# DDMTD.net
KiCad netlist of a schematic drawn in Altium Designer
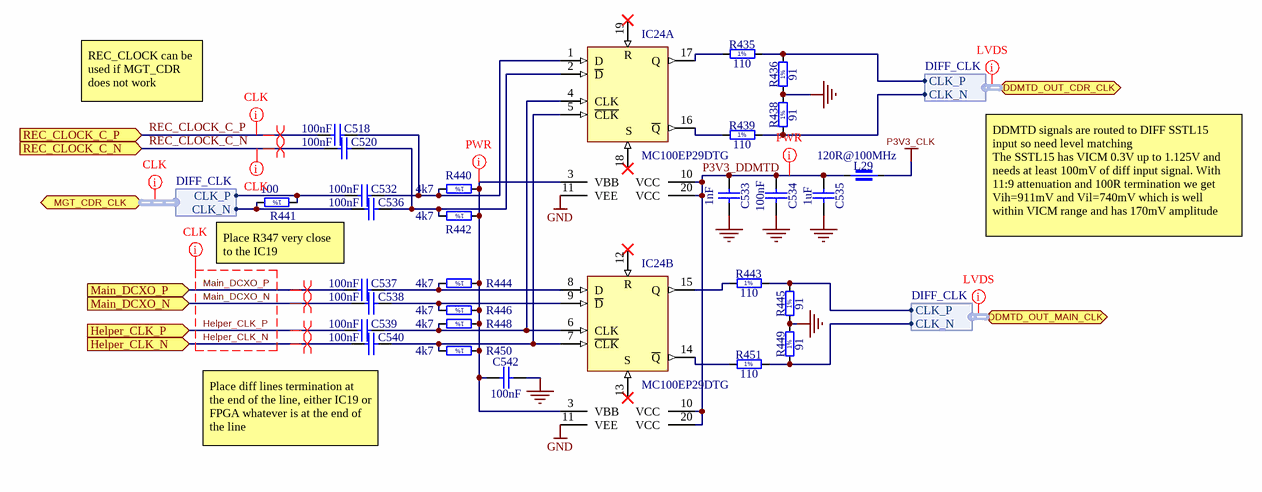
[diagram p0: DDMTD.SchDoc]

(export (version "E")
  (design (tool "Eeschema 10.0.6"))
  (components
    (comp (ref "C518")
      (value "100nF")
      (footprint "CAPC1005X55N")
      (description "Non-polarised capacitor")
      (fields
        (field (name "MANUFACTURER PART NUMBER") "CC0402_100NF_16V_10%_X5R")
        (field (name "MANUFACTURER") "GENERIC")
        (field (name "AUTHOR") "CERN DEM JLC")
      )
      (libsource (lib "Capacitors") (part "Capacitor - non polarized"))
    )
    (comp (ref "C520")
      (value "100nF")
      (footprint "CAPC1005X55N")
      (description "Non-polarised capacitor")
      (fields
        (field (name "MANUFACTURER PART NUMBER") "CC0402_100NF_16V_10%_X5R")
        (field (name "MANUFACTURER") "GENERIC")
        (field (name "AUTHOR") "CERN DEM JLC")
      )
      (libsource (lib "Capacitors") (part "Capacitor - non polarized"))
    )
    (comp (ref "C532")
      (value "100nF")
      (footprint "CAPC1005X55N")
      (description "Non-polarised capacitor")
      (fields
        (field (name "MANUFACTURER PART NUMBER") "CC0402_100NF_16V_10%_X5R")
        (field (name "MANUFACTURER") "GENERIC")
        (field (name "AUTHOR") "CERN DEM JLC")
      )
      (libsource (lib "Capacitors") (part "Capacitor - non polarized"))
    )
    (comp (ref "C533")
      (value "1nF")
      (footprint "CAPC0603X33N")
      (description "Non-polarised capacitor")
      (fields
        (field (name "MANUFACTURER PART NUMBER") "CC0201_1NF_16V_10%_X5R")
        (field (name "MANUFACTURER") "GENERIC")
        (field (name "AUTHOR") "CERN DEM JLC")
      )
      (libsource (lib "Capacitors") (part "Capacitor - non polarized"))
    )
    (comp (ref "C534")
      (value "100nF")
      (footprint "CAPC0603X33N")
      (description "Non-polarised capacitor")
      (fields
        (field (name "MANUFACTURER PART NUMBER") "CC0201_100NF_6.3V_10%_X5R")
        (field (name "MANUFACTURER") "GENERIC")
        (field (name "AUTHOR") "CERN DEM JLC")
      )
      (libsource (lib "Capacitors") (part "Capacitor - non polarized"))
    )
    (comp (ref "C535")
      (value "1uF")
      (footprint "CAPC1005X55N")
      (description "Non-polarised capacitor")
      (fields
        (field (name "MANUFACTURER PART NUMBER") "CC0402_1UF_16V_10%_X5R")
        (field (name "MANUFACTURER") "GENERIC")
        (field (name "AUTHOR") "CERN DEM JLC")
      )
      (libsource (lib "Capacitors") (part "Capacitor - non polarized"))
    )
    (comp (ref "C536")
      (value "100nF")
      (footprint "CAPC1005X55N")
      (description "Non-polarised capacitor")
      (fields
        (field (name "MANUFACTURER PART NUMBER") "CC0402_100NF_16V_10%_X5R")
        (field (name "MANUFACTURER") "GENERIC")
        (field (name "AUTHOR") "CERN DEM JLC")
      )
      (libsource (lib "Capacitors") (part "Capacitor - non polarized"))
    )
    (comp (ref "C537")
      (value "100nF")
      (footprint "CAPC1005X55N")
      (description "Non-polarised capacitor")
      (fields
        (field (name "MANUFACTURER PART NUMBER") "CC0402_100NF_16V_10%_X5R")
        (field (name "MANUFACTURER") "GENERIC")
        (field (name "AUTHOR") "CERN DEM JLC")
      )
      (libsource (lib "Capacitors") (part "Capacitor - non polarized"))
    )
    (comp (ref "C538")
      (value "100nF")
      (footprint "CAPC1005X55N")
      (description "Non-polarised capacitor")
      (fields
        (field (name "MANUFACTURER PART NUMBER") "CC0402_100NF_16V_10%_X5R")
        (field (name "MANUFACTURER") "GENERIC")
        (field (name "AUTHOR") "CERN DEM JLC")
      )
      (libsource (lib "Capacitors") (part "Capacitor - non polarized"))
    )
    (comp (ref "C539")
      (value "100nF")
      (footprint "CAPC1005X55N")
      (description "Non-polarised capacitor")
      (fields
        (field (name "MANUFACTURER PART NUMBER") "CC0402_100NF_16V_10%_X5R")
        (field (name "MANUFACTURER") "GENERIC")
        (field (name "AUTHOR") "CERN DEM JLC")
      )
      (libsource (lib "Capacitors") (part "Capacitor - non polarized"))
    )
    (comp (ref "C540")
      (value "100nF")
      (footprint "CAPC1005X55N")
      (description "Non-polarised capacitor")
      (fields
        (field (name "MANUFACTURER PART NUMBER") "CC0402_100NF_16V_10%_X5R")
        (field (name "MANUFACTURER") "GENERIC")
        (field (name "AUTHOR") "CERN DEM JLC")
      )
      (libsource (lib "Capacitors") (part "Capacitor - non polarized"))
    )
    (comp (ref "C542")
      (value "100nF")
      (footprint "CAPC0603X33N")
      (description "Non-polarised capacitor")
      (fields
        (field (name "MANUFACTURER PART NUMBER") "CC0201_100NF_6.3V_10%_X5R")
        (field (name "MANUFACTURER") "GENERIC")
        (field (name "AUTHOR") "CERN DEM JLC")
      )
      (libsource (lib "Capacitors") (part "Capacitor - non polarized"))
    )
    (comp (ref "IC24")
      (value "MC100EP29DTG")
      (footprint "SOP65P640X120-20N")
      (description "3.3V/5V ECL Dual Differential Data and Clock D Flip-Flop With Set and Reset")
      (fields (field (name "MANUFACTURER") "ON SEMICONDUCTOR") (field (name "AUTHOR") "CERN DEM JLC"))
      (libsource (lib "ICs And Semiconductors") (part "100EP29D"))
    )
    (comp (ref "L29")
      (value "120R@100MHz")
      (footprint "INDC1608X95N")
      (fields
        (field (name "MANUFACTURER PART NUMBER") "BLM18PG121SN1D")
        (field (name "MANUFACTURER") "MURATA")
        (field (name "PART NUMBER") "IND0603_MURATA_BLM18PG121SN1D")
        (field (name "AUTHOR") "CERN DEM BC")
      )
      (libsource (lib "Inductors & Transformers") (part "Ferrite Bead"))
    )
    (comp (ref "R435")
      (value "110")
      (footprint "RESC1005X40N")
      (description "Resistor - 1%")
      (fields
        (field (name "MANUFACTURER PART NUMBER") "R0402_110R_1%_0.0625W_100PPM")
        (field (name "MANUFACTURER") "GENERIC")
        (field (name "AUTHOR") "CERN DEM JLC")
      )
      (libsource (lib "Resistors") (part "Resistor - 1%"))
    )
    (comp (ref "R436")
      (value "91")
      (footprint "RESC1005X40N")
      (description "Resistor - 1%")
      (fields
        (field (name "MANUFACTURER PART NUMBER") "R0402_91R_1%_0.0625W_100PPM")
        (field (name "MANUFACTURER") "GENERIC")
        (field (name "AUTHOR") "CERN DEM JLC")
      )
      (libsource (lib "Resistors") (part "Resistor - 1%"))
    )
    (comp (ref "R438")
      (value "91")
      (footprint "RESC1005X40N")
      (description "Resistor - 1%")
      (fields
        (field (name "MANUFACTURER PART NUMBER") "R0402_91R_1%_0.0625W_100PPM")
        (field (name "MANUFACTURER") "GENERIC")
        (field (name "AUTHOR") "CERN DEM JLC")
      )
      (libsource (lib "Resistors") (part "Resistor - 1%"))
    )
    (comp (ref "R439")
      (value "110")
      (footprint "RESC1005X40N")
      (description "Resistor - 1%")
      (fields
        (field (name "MANUFACTURER PART NUMBER") "R0402_110R_1%_0.0625W_100PPM")
        (field (name "MANUFACTURER") "GENERIC")
        (field (name "AUTHOR") "CERN DEM JLC")
      )
      (libsource (lib "Resistors") (part "Resistor - 1%"))
    )
    (comp (ref "R440")
      (value "4k7")
      (footprint "RESC1005X40N")
      (description "Resistor - 1%")
      (fields
        (field (name "MANUFACTURER PART NUMBER") "R0402_4K7_1%_0.0625W_100PPM")
        (field (name "MANUFACTURER") "GENERIC")
        (field (name "AUTHOR") "CERN DEM JLC")
      )
      (libsource (lib "Resistors") (part "Resistor - 1%"))
    )
    (comp (ref "R441")
      (value "100")
      (footprint "RESC1005X40N")
      (description "Resistor - 1%")
      (fields
        (field (name "MANUFACTURER PART NUMBER") "R0402_100R_1%_0.0625W_100PPM")
        (field (name "MANUFACTURER") "GENERIC")
        (field (name "AUTHOR") "CERN DEM JLC")
      )
      (libsource (lib "Resistors") (part "Resistor - 1%"))
    )
    (comp (ref "R442")
      (value "4k7")
      (footprint "RESC1005X40N")
      (description "Resistor - 1%")
      (fields
        (field (name "MANUFACTURER PART NUMBER") "R0402_4K7_1%_0.0625W_100PPM")
        (field (name "MANUFACTURER") "GENERIC")
        (field (name "AUTHOR") "CERN DEM JLC")
      )
      (libsource (lib "Resistors") (part "Resistor - 1%"))
    )
    (comp (ref "R443")
      (value "110")
      (footprint "RESC1005X40N")
      (description "Resistor - 1%")
      (fields
        (field (name "MANUFACTURER PART NUMBER") "R0402_110R_1%_0.0625W_100PPM")
        (field (name "MANUFACTURER") "GENERIC")
        (field (name "AUTHOR") "CERN DEM JLC")
      )
      (libsource (lib "Resistors") (part "Resistor - 1%"))
    )
    (comp (ref "R444")
      (value "4k7")
      (footprint "RESC1005X40N")
      (description "Resistor - 1%")
      (fields
        (field (name "MANUFACTURER PART NUMBER") "R0402_4K7_1%_0.0625W_100PPM")
        (field (name "MANUFACTURER") "GENERIC")
        (field (name "AUTHOR") "CERN DEM JLC")
      )
      (libsource (lib "Resistors") (part "Resistor - 1%"))
    )
    (comp (ref "R445")
      (value "91")
      (footprint "RESC1005X40N")
      (description "Resistor - 1%")
      (fields
        (field (name "MANUFACTURER PART NUMBER") "R0402_91R_1%_0.0625W_100PPM")
        (field (name "MANUFACTURER") "GENERIC")
        (field (name "AUTHOR") "CERN DEM JLC")
      )
      (libsource (lib "Resistors") (part "Resistor - 1%"))
    )
    (comp (ref "R446")
      (value "4k7")
      (footprint "RESC1005X40N")
      (description "Resistor - 1%")
      (fields
        (field (name "MANUFACTURER PART NUMBER") "R0402_4K7_1%_0.0625W_100PPM")
        (field (name "MANUFACTURER") "GENERIC")
        (field (name "AUTHOR") "CERN DEM JLC")
      )
      (libsource (lib "Resistors") (part "Resistor - 1%"))
    )
    (comp (ref "R448")
      (value "4k7")
      (footprint "RESC1005X40N")
      (description "Resistor - 1%")
      (fields
        (field (name "MANUFACTURER PART NUMBER") "R0402_4K7_1%_0.0625W_100PPM")
        (field (name "MANUFACTURER") "GENERIC")
        (field (name "AUTHOR") "CERN DEM JLC")
      )
      (libsource (lib "Resistors") (part "Resistor - 1%"))
    )
    (comp (ref "R449")
      (value "91")
      (footprint "RESC1005X40N")
      (description "Resistor - 1%")
      (fields
        (field (name "MANUFACTURER PART NUMBER") "R0402_91R_1%_0.0625W_100PPM")
        (field (name "MANUFACTURER") "GENERIC")
        (field (name "AUTHOR") "CERN DEM JLC")
      )
      (libsource (lib "Resistors") (part "Resistor - 1%"))
    )
    (comp (ref "R450")
      (value "4k7")
      (footprint "RESC1005X40N")
      (description "Resistor - 1%")
      (fields
        (field (name "MANUFACTURER PART NUMBER") "R0402_4K7_1%_0.0625W_100PPM")
        (field (name "MANUFACTURER") "GENERIC")
        (field (name "AUTHOR") "CERN DEM JLC")
      )
      (libsource (lib "Resistors") (part "Resistor - 1%"))
    )
    (comp (ref "R451")
      (value "110")
      (footprint "RESC1005X40N")
      (description "Resistor - 1%")
      (fields
        (field (name "MANUFACTURER PART NUMBER") "R0402_110R_1%_0.0625W_100PPM")
        (field (name "MANUFACTURER") "GENERIC")
        (field (name "AUTHOR") "CERN DEM JLC")
      )
      (libsource (lib "Resistors") (part "Resistor - 1%"))
    )
  )
  (nets
    (net (code "2") (name "/Helper_CLK_N") (class "Default")
      (node (ref "C540") (pin "1") (pinfunction "1_1") (pintype "passive"))
    )
    (net (code "3") (name "/Helper_CLK_P") (class "Default")
      (node (ref "C539") (pin "1") (pinfunction "1_1") (pintype "passive"))
    )
    (net (code "4") (name "/Main_DCXO_N") (class "Default")
      (node (ref "C538") (pin "1") (pinfunction "1_1") (pintype "passive"))
    )
    (net (code "5") (name "/Main_DCXO_P") (class "Default")
      (node (ref "C537") (pin "1") (pinfunction "1_1") (pintype "passive"))
    )
    (net (code "6") (name "/P3V3_DDMTD") (class "Default")
      (node (ref "C533") (pin "2") (pinfunction "2_2") (pintype "passive"))
      (node (ref "C534") (pin "2") (pinfunction "2_2") (pintype "passive"))
      (node (ref "C535") (pin "1") (pinfunction "1_1") (pintype "passive"))
      (node (ref "IC24") (pin "10") (pinfunction "VCC_10") (pintype "power_in"))
      (node (ref "IC24") (pin "20") (pinfunction "VCC_20") (pintype "power_in"))
      (node (ref "L29") (pin "2") (pinfunction "2_2") (pintype "passive"))
    )
    (net (code "7") (name "/REC_CLOCK_C_N") (class "Default")
      (node (ref "C520") (pin "1") (pinfunction "1_1") (pintype "passive"))
    )
    (net (code "8") (name "/REC_CLOCK_C_P") (class "Default")
      (node (ref "C518") (pin "1") (pinfunction "1_1") (pintype "passive"))
    )
    (net (code "10") (name "GND") (class "Default")
      (node (ref "C533") (pin "1") (pinfunction "1_1") (pintype "passive"))
      (node (ref "C534") (pin "1") (pinfunction "1_1") (pintype "passive"))
      (node (ref "C535") (pin "2") (pinfunction "2_2") (pintype "passive"))
      (node (ref "C542") (pin "1") (pinfunction "1_1") (pintype "passive"))
      (node (ref "IC24") (pin "11") (pinfunction "VEE_11") (pintype "power_in"))
      (node (ref "R436") (pin "1") (pinfunction "1_1") (pintype "passive"))
      (node (ref "R438") (pin "2") (pinfunction "2_2") (pintype "passive"))
      (node (ref "R445") (pin "1") (pinfunction "1_1") (pintype "passive"))
      (node (ref "R449") (pin "2") (pinfunction "2_2") (pintype "passive"))
    )
    (net (code "11") (name "Net-(C532-Pad1)") (class "Default")
      (node (ref "C532") (pin "1") (pinfunction "1_1") (pintype "passive"))
      (node (ref "R441") (pin "1") (pinfunction "1_1") (pintype "passive"))
    )
    (net (code "12") (name "Net-(C536-Pad1)") (class "Default")
      (node (ref "C536") (pin "1") (pinfunction "1_1") (pintype "passive"))
      (node (ref "R441") (pin "2") (pinfunction "2_2") (pintype "passive"))
    )
    (net (code "13") (name "Net-(IC24A-CLK)") (class "Default")
      (node (ref "C539") (pin "2") (pinfunction "2_2") (pintype "passive"))
      (node (ref "IC24") (pin "4") (pinfunction "CLK_4") (pintype "input"))
      (node (ref "IC24") (pin "6") (pinfunction "CLK_6") (pintype "input"))
      (node (ref "R448") (pin "2") (pinfunction "2_2") (pintype "passive"))
    )
    (net (code "14") (name "Net-(IC24A-D)") (class "Default")
      (node (ref "C518") (pin "2") (pinfunction "2_2") (pintype "passive"))
      (node (ref "C532") (pin "2") (pinfunction "2_2") (pintype "passive"))
      (node (ref "IC24") (pin "1") (pinfunction "D_1") (pintype "input"))
      (node (ref "R440") (pin "2") (pinfunction "2_2") (pintype "passive"))
    )
    (net (code "15") (name "Net-(IC24A-Q)") (class "Default")
      (node (ref "IC24") (pin "17") (pinfunction "Q_17") (pintype "output"))
      (node (ref "R435") (pin "1") (pinfunction "1_1") (pintype "passive"))
    )
    (net (code "16") (name "Net-(IC24A-VBB)") (class "Default")
      (node (ref "C542") (pin "2") (pinfunction "2_2") (pintype "passive"))
      (node (ref "IC24") (pin "3") (pinfunction "VBB_3") (pintype "power_in"))
      (node (ref "R440") (pin "1") (pinfunction "1_1") (pintype "passive"))
      (node (ref "R442") (pin "1") (pinfunction "1_1") (pintype "passive"))
      (node (ref "R444") (pin "1") (pinfunction "1_1") (pintype "passive"))
      (node (ref "R446") (pin "1") (pinfunction "1_1") (pintype "passive"))
      (node (ref "R448") (pin "1") (pinfunction "1_1") (pintype "passive"))
      (node (ref "R450") (pin "1") (pinfunction "1_1") (pintype "passive"))
    )
    (net (code "17") (name "Net-(IC24A-~{CLK})") (class "Default")
      (node (ref "C540") (pin "2") (pinfunction "2_2") (pintype "passive"))
      (node (ref "IC24") (pin "5") (pinfunction "~{CLK}_5") (pintype "input"))
      (node (ref "IC24") (pin "7") (pinfunction "~{CLK}_7") (pintype "input"))
      (node (ref "R450") (pin "2") (pinfunction "2_2") (pintype "passive"))
    )
    (net (code "18") (name "Net-(IC24A-~{D})") (class "Default")
      (node (ref "C520") (pin "2") (pinfunction "2_2") (pintype "passive"))
      (node (ref "C536") (pin "2") (pinfunction "2_2") (pintype "passive"))
      (node (ref "IC24") (pin "2") (pinfunction "~{D}_2") (pintype "input"))
      (node (ref "R442") (pin "2") (pinfunction "2_2") (pintype "passive"))
    )
    (net (code "19") (name "Net-(IC24A-~{Q})") (class "Default")
      (node (ref "IC24") (pin "16") (pinfunction "~{Q}_16") (pintype "output"))
      (node (ref "R439") (pin "1") (pinfunction "1_1") (pintype "passive"))
    )
    (net (code "20") (name "Net-(IC24B-D)") (class "Default")
      (node (ref "C537") (pin "2") (pinfunction "2_2") (pintype "passive"))
      (node (ref "IC24") (pin "8") (pinfunction "D_8") (pintype "input"))
      (node (ref "R444") (pin "2") (pinfunction "2_2") (pintype "passive"))
    )
    (net (code "21") (name "Net-(IC24B-Q)") (class "Default")
      (node (ref "IC24") (pin "15") (pinfunction "Q_15") (pintype "output"))
      (node (ref "R443") (pin "1") (pinfunction "1_1") (pintype "passive"))
    )
    (net (code "22") (name "Net-(IC24B-~{D})") (class "Default")
      (node (ref "C538") (pin "2") (pinfunction "2_2") (pintype "passive"))
      (node (ref "IC24") (pin "9") (pinfunction "~{D}_9") (pintype "input"))
      (node (ref "R446") (pin "2") (pinfunction "2_2") (pintype "passive"))
    )
    (net (code "23") (name "Net-(IC24B-~{Q})") (class "Default")
      (node (ref "IC24") (pin "14") (pinfunction "~{Q}_14") (pintype "output"))
      (node (ref "R451") (pin "1") (pinfunction "1_1") (pintype "passive"))
    )
    (net (code "24") (name "Net-(R435-Pad2)") (class "Default")
      (node (ref "R435") (pin "2") (pinfunction "2_2") (pintype "passive"))
      (node (ref "R436") (pin "2") (pinfunction "2_2") (pintype "passive"))
    )
    (net (code "25") (name "Net-(R438-Pad1)") (class "Default")
      (node (ref "R438") (pin "1") (pinfunction "1_1") (pintype "passive"))
      (node (ref "R439") (pin "2") (pinfunction "2_2") (pintype "passive"))
    )
    (net (code "26") (name "Net-(R443-Pad2)") (class "Default")
      (node (ref "R443") (pin "2") (pinfunction "2_2") (pintype "passive"))
      (node (ref "R445") (pin "2") (pinfunction "2_2") (pintype "passive"))
    )
    (net (code "27") (name "Net-(R449-Pad1)") (class "Default")
      (node (ref "R449") (pin "1") (pinfunction "1_1") (pintype "passive"))
      (node (ref "R451") (pin "2") (pinfunction "2_2") (pintype "passive"))
    )
    (net (code "28") (name "P3V3_CLK") (class "Default")
      (node (ref "L29") (pin "1") (pinfunction "1_1") (pintype "passive"))
    )
    (net (code "29") (name "unconnected-(IC24A-R-Pad19)") (class "Default")
      (node (ref "IC24") (pin "19") (pinfunction "R_19") (pintype "input+no_connect"))
    )
    (net (code "30") (name "unconnected-(IC24A-S-Pad18)") (class "Default")
      (node (ref "IC24") (pin "18") (pinfunction "S_18") (pintype "input+no_connect"))
    )
    (net (code "31") (name "unconnected-(IC24B-R-Pad12)") (class "Default")
      (node (ref "IC24") (pin "12") (pinfunction "R_12") (pintype "input+no_connect"))
    )
    (net (code "32") (name "unconnected-(IC24B-S-Pad13)") (class "Default")
      (node (ref "IC24") (pin "13") (pinfunction "S_13") (pintype "input+no_connect"))
    )
  )
)
